# MCU.net
KiCad netlist of a schematic drawn in Altium Designer
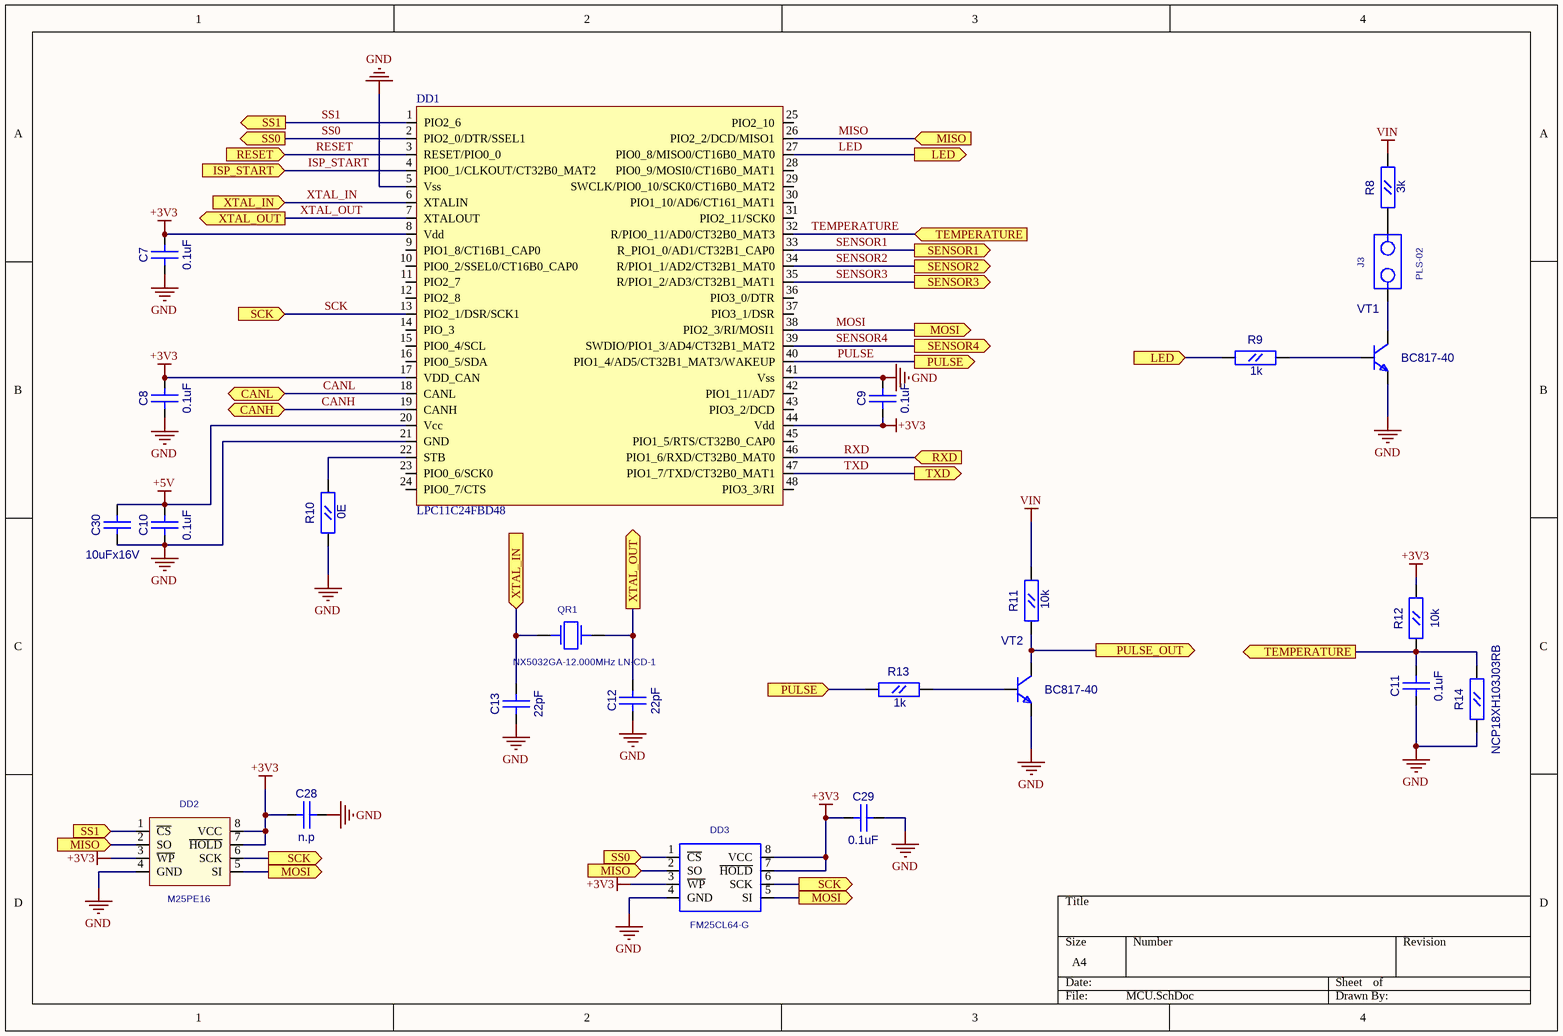
[diagram p0: MCU.SchDoc]

(export (version "E")
  (design (tool "Eeschema 10.0.6"))
  (components
    (comp (ref "C7")
      (value "0.1uF")
      (footprint "CC0603")
      (description "CC0603")
      (libsource (lib "gprs_modem_2") (part "CC0603"))
    )
    (comp (ref "C8")
      (value "0.1uF")
      (footprint "CC0603")
      (description "CC0603")
      (libsource (lib "gprs_modem_2") (part "CC0603"))
    )
    (comp (ref "C9")
      (value "0.1uF")
      (footprint "CC0603")
      (description "CC0603")
      (libsource (lib "gprs_modem_2") (part "CC0603"))
    )
    (comp (ref "C10")
      (value "0.1uF")
      (footprint "CC0603")
      (description "CC0603")
      (libsource (lib "gprs_modem_2") (part "CC0603"))
    )
    (comp (ref "C11")
      (value "0.1uF")
      (footprint "CC0603")
      (description "CC0603")
      (libsource (lib "gprs_modem_2") (part "CC0603"))
    )
    (comp (ref "C12")
      (value "22pF")
      (footprint "CC0603")
      (description "CC0603")
      (libsource (lib "gprs_modem_2") (part "CC0603"))
    )
    (comp (ref "C13")
      (value "22pF")
      (footprint "CC0603")
      (description "CC0603")
      (libsource (lib "gprs_modem_2") (part "CC0603"))
    )
    (comp (ref "C28")
      (value "n.p")
      (footprint "CC0603")
      (description "CC0603")
      (libsource (lib "gprs_modem_2") (part "CC0603"))
    )
    (comp (ref "C29")
      (value "0.1uF")
      (footprint "CC0603")
      (description "CC0603")
      (libsource (lib "gprs_modem_2") (part "CC0603"))
    )
    (comp (ref "C30")
      (value "10uFx16V")
      (footprint "CC0805")
      (description "CC0805")
      (libsource (lib "gprs_modem_2") (part "CC0805"))
    )
    (comp (ref "DD1")
      (value "LPC11C24FBD48")
      (footprint "LQFP-48")
      (libsource (lib "gprs_modem_2") (part "LPC11C24FBD48"))
    )
    (comp (ref "DD2")
      (value "M25PE16")
      (footprint "EIAJ_SO8")
      (description "S25FL016A0LMFI01")
      (libsource (lib "gprs_modem_2") (part "S25FL016A0LMFI01"))
    )
    (comp (ref "DD3")
      (value "FM25CL64-G")
      (footprint "SO-8")
      (libsource (lib "gprs_modem_2") (part "FM25CL64-G"))
    )
    (comp (ref "J3") (value "PLS-02") (footprint "PLS-02") (libsource (lib "gprs_modem_2") (part "PLS-02")))
    (comp (ref "QR1")
      (value "NX5032GA-12.000MHz LN-CD-1")
      (footprint "AC5032_2")
      (description "AC5032/2")
      (libsource (lib "gprs_modem_2") (part "AC5032_2"))
    )
    (comp (ref "R8")
      (value "3k")
      (footprint "RC0603")
      (description "RC0603")
      (libsource (lib "gprs_modem_2") (part "RC0603"))
    )
    (comp (ref "R9")
      (value "1k")
      (footprint "RC0603")
      (description "RC0603")
      (libsource (lib "gprs_modem_2") (part "RC0603"))
    )
    (comp (ref "R10")
      (value "0E")
      (footprint "RC0603")
      (description "RC0603")
      (libsource (lib "gprs_modem_2") (part "RC0603"))
    )
    (comp (ref "R11")
      (value "10k")
      (footprint "RC0603")
      (description "RC0603")
      (libsource (lib "gprs_modem_2") (part "RC0603"))
    )
    (comp (ref "R12")
      (value "10k")
      (footprint "RC0603")
      (description "RC0603")
      (libsource (lib "gprs_modem_2") (part "RC0603"))
    )
    (comp (ref "R13")
      (value "1k")
      (footprint "RC0603")
      (description "RC0603")
      (libsource (lib "gprs_modem_2") (part "RC0603"))
    )
    (comp (ref "R14")
      (value "NCP18XH103J03RB")
      (footprint "RC0603")
      (description "RC0603")
      (libsource (lib "gprs_modem_2") (part "RC0603"))
    )
    (comp (ref "VT1")
      (value "BC817-40")
      (footprint "SOT-23(123)")
      (description "NPN 500ma transistor")
      (libsource (lib "gprs_modem_2") (part "BC846BLT1"))
    )
    (comp (ref "VT2")
      (value "BC817-40")
      (footprint "SOT-23(123)")
      (description "NPN 500ma transistor")
      (libsource (lib "gprs_modem_2") (part "BC846BLT1"))
    )
  )
  (nets
    (net (code "1") (name "+3V3") (class "Default")
      (node (ref "C28") (pin "1") (pinfunction "A_1") (pintype "passive"))
      (node (ref "C29") (pin "1") (pinfunction "A_1") (pintype "passive"))
      (node (ref "C7") (pin "2") (pinfunction "B_2") (pintype "passive"))
      (node (ref "C8") (pin "2") (pinfunction "B_2") (pintype "passive"))
      (node (ref "C9") (pin "1") (pinfunction "A_1") (pintype "passive"))
      (node (ref "DD1") (pin "17") (pinfunction "VDD_CAN_17") (pintype "passive"))
      (node (ref "DD1") (pin "44") (pinfunction "Vdd_44") (pintype "passive"))
      (node (ref "DD1") (pin "8") (pinfunction "Vdd_8") (pintype "passive"))
      (node (ref "DD2") (pin "3") (pinfunction "~{WP}_3") (pintype "passive"))
      (node (ref "DD2") (pin "7") (pinfunction "~{HOLD}_7") (pintype "passive"))
      (node (ref "DD2") (pin "8") (pinfunction "VCC_8") (pintype "passive"))
      (node (ref "DD3") (pin "3") (pinfunction "~{WP}_3") (pintype "passive"))
      (node (ref "DD3") (pin "7") (pinfunction "~{HOLD}_7") (pintype "passive"))
      (node (ref "DD3") (pin "8") (pinfunction "VCC_8") (pintype "passive"))
      (node (ref "R12") (pin "2") (pinfunction "B_2") (pintype "passive"))
    )
    (net (code "2") (name "+5V") (class "Default")
      (node (ref "C10") (pin "2") (pinfunction "B_2") (pintype "passive"))
      (node (ref "C30") (pin "2") (pinfunction "B_2") (pintype "passive"))
      (node (ref "DD1") (pin "20") (pinfunction "Vcc_20") (pintype "passive"))
    )
    (net (code "3") (name "/CANH") (class "Default")
      (node (ref "DD1") (pin "19") (pinfunction "CANH_19") (pintype "passive"))
    )
    (net (code "4") (name "/CANL") (class "Default")
      (node (ref "DD1") (pin "18") (pinfunction "CANL_18") (pintype "passive"))
    )
    (net (code "5") (name "/ISP_START") (class "Default")
      (node (ref "DD1") (pin "4") (pinfunction "PIO0_1/CLKOUT/CT32B0_MAT2_4") (pintype "passive"))
    )
    (net (code "6") (name "/LED") (class "Default")
      (node (ref "DD1") (pin "27") (pinfunction "PIO0_8/MISO0/CT16B0_MAT0_27") (pintype "passive"))
      (node (ref "R9") (pin "1") (pinfunction "A_1") (pintype "passive"))
    )
    (net (code "7") (name "/MISO") (class "Default")
      (node (ref "DD1") (pin "26") (pinfunction "PIO2_2/DCD/MISO1_26") (pintype "passive"))
      (node (ref "DD2") (pin "2") (pinfunction "SO_2") (pintype "passive"))
      (node (ref "DD3") (pin "2") (pinfunction "SO_2") (pintype "passive"))
    )
    (net (code "8") (name "/MOSI") (class "Default")
      (node (ref "DD1") (pin "38") (pinfunction "PIO2_3/RI/MOSI1_38") (pintype "passive"))
      (node (ref "DD2") (pin "5") (pinfunction "SI_5") (pintype "passive"))
      (node (ref "DD3") (pin "5") (pinfunction "SI_5") (pintype "passive"))
    )
    (net (code "9") (name "/PULSE") (class "Default")
      (node (ref "DD1") (pin "40") (pinfunction "PIO1_4/AD5/CT32B1_MAT3/WAKEUP_40") (pintype "passive"))
      (node (ref "R13") (pin "1") (pinfunction "A_1") (pintype "passive"))
    )
    (net (code "10") (name "/PULSE_OUT") (class "Default")
      (node (ref "R11") (pin "1") (pinfunction "A_1") (pintype "passive"))
      (node (ref "VT2") (pin "3") (pinfunction "C_3") (pintype "passive"))
    )
    (net (code "11") (name "/RESET") (class "Default")
      (node (ref "DD1") (pin "3") (pinfunction "RESET/PIO0_0_3") (pintype "passive"))
    )
    (net (code "12") (name "/RXD") (class "Default")
      (node (ref "DD1") (pin "46") (pinfunction "PIO1_6/RXD/CT32B0_MAT0_46") (pintype "passive"))
    )
    (net (code "13") (name "/SCK") (class "Default")
      (node (ref "DD1") (pin "13") (pinfunction "PIO2_1/DSR/SCK1_13") (pintype "passive"))
      (node (ref "DD2") (pin "6") (pinfunction "SCK_6") (pintype "passive"))
      (node (ref "DD3") (pin "6") (pinfunction "SCK_6") (pintype "passive"))
    )
    (net (code "14") (name "/SENSOR1") (class "Default")
      (node (ref "DD1") (pin "33") (pinfunction "R_PIO1_0/AD1/CT32B1_CAP0_33") (pintype "passive"))
    )
    (net (code "15") (name "/SENSOR2") (class "Default")
      (node (ref "DD1") (pin "34") (pinfunction "R/PIO1_1/AD2/CT32B1_MAT0_34") (pintype "passive"))
    )
    (net (code "16") (name "/SENSOR3") (class "Default")
      (node (ref "DD1") (pin "35") (pinfunction "R/PIO1_2/AD3/CT32B1_MAT1_35") (pintype "passive"))
    )
    (net (code "17") (name "/SENSOR4") (class "Default")
      (node (ref "DD1") (pin "39") (pinfunction "SWDIO/PIO1_3/AD4/CT32B1_MAT2_39") (pintype "passive"))
    )
    (net (code "18") (name "/SS0") (class "Default")
      (node (ref "DD1") (pin "2") (pinfunction "PIO2_0/DTR/SSEL1_2") (pintype "passive"))
      (node (ref "DD3") (pin "1") (pinfunction "~{CS}_1") (pintype "passive"))
    )
    (net (code "19") (name "/SS1") (class "Default")
      (node (ref "DD1") (pin "1") (pinfunction "PIO2_6_1") (pintype "passive"))
      (node (ref "DD2") (pin "1") (pinfunction "~{CS}_1") (pintype "passive"))
    )
    (net (code "20") (name "/TEMPERATURE") (class "Default")
      (node (ref "C11") (pin "2") (pinfunction "B_2") (pintype "passive"))
      (node (ref "DD1") (pin "32") (pinfunction "R/PIO0_11/AD0/CT32B0_MAT3_32") (pintype "passive"))
      (node (ref "R12") (pin "1") (pinfunction "A_1") (pintype "passive"))
      (node (ref "R14") (pin "2") (pinfunction "B_2") (pintype "passive"))
    )
    (net (code "21") (name "/TXD") (class "Default")
      (node (ref "DD1") (pin "47") (pinfunction "PIO1_7/TXD/CT32B0_MAT1_47") (pintype "passive"))
    )
    (net (code "22") (name "/XTAL_IN") (class "Default")
      (node (ref "C13") (pin "2") (pinfunction "B_2") (pintype "passive"))
      (node (ref "DD1") (pin "6") (pinfunction "XTALIN_6") (pintype "passive"))
      (node (ref "QR1") (pin "1") (pintype "passive"))
    )
    (net (code "23") (name "/XTAL_OUT") (class "Default")
      (node (ref "C12") (pin "2") (pinfunction "B_2") (pintype "passive"))
      (node (ref "DD1") (pin "7") (pinfunction "XTALOUT_7") (pintype "passive"))
      (node (ref "QR1") (pin "2") (pintype "passive"))
    )
    (net (code "24") (name "GND") (class "Default")
      (node (ref "C10") (pin "1") (pinfunction "A_1") (pintype "passive"))
      (node (ref "C11") (pin "1") (pinfunction "A_1") (pintype "passive"))
      (node (ref "C12") (pin "1") (pinfunction "A_1") (pintype "passive"))
      (node (ref "C13") (pin "1") (pinfunction "A_1") (pintype "passive"))
      (node (ref "C28") (pin "2") (pinfunction "B_2") (pintype "passive"))
      (node (ref "C29") (pin "2") (pinfunction "B_2") (pintype "passive"))
      (node (ref "C30") (pin "1") (pinfunction "A_1") (pintype "passive"))
      (node (ref "C7") (pin "1") (pinfunction "A_1") (pintype "passive"))
      (node (ref "C8") (pin "1") (pinfunction "A_1") (pintype "passive"))
      (node (ref "C9") (pin "2") (pinfunction "B_2") (pintype "passive"))
      (node (ref "DD1") (pin "21") (pinfunction "GND_21") (pintype "passive"))
      (node (ref "DD1") (pin "41") (pinfunction "Vss_41") (pintype "passive"))
      (node (ref "DD1") (pin "5") (pinfunction "Vss_5") (pintype "passive"))
      (node (ref "DD2") (pin "4") (pinfunction "GND_4") (pintype "passive"))
      (node (ref "DD3") (pin "4") (pinfunction "GND_4") (pintype "passive"))
      (node (ref "R10") (pin "1") (pinfunction "A_1") (pintype "passive"))
      (node (ref "R14") (pin "1") (pinfunction "A_1") (pintype "passive"))
      (node (ref "VT1") (pin "2") (pinfunction "E_2") (pintype "passive"))
      (node (ref "VT2") (pin "2") (pinfunction "E_2") (pintype "passive"))
    )
    (net (code "25") (name "Net-(DD1-STB)") (class "Default")
      (node (ref "DD1") (pin "22") (pinfunction "STB_22") (pintype "passive"))
      (node (ref "R10") (pin "2") (pinfunction "B_2") (pintype "passive"))
    )
    (net (code "26") (name "Net-(R8-A)") (class "Default")
      (node (ref "J3") (pin "2") (pintype "passive"))
      (node (ref "R8") (pin "1") (pinfunction "A_1") (pintype "passive"))
    )
    (net (code "27") (name "Net-(R9-B)") (class "Default")
      (node (ref "R9") (pin "2") (pinfunction "B_2") (pintype "passive"))
      (node (ref "VT1") (pin "1") (pinfunction "B_1") (pintype "passive"))
    )
    (net (code "28") (name "Net-(R13-B)") (class "Default")
      (node (ref "R13") (pin "2") (pinfunction "B_2") (pintype "passive"))
      (node (ref "VT2") (pin "1") (pinfunction "B_1") (pintype "passive"))
    )
    (net (code "29") (name "Net-(VT1-C)") (class "Default")
      (node (ref "J3") (pin "1") (pintype "passive"))
      (node (ref "VT1") (pin "3") (pinfunction "C_3") (pintype "passive"))
    )
    (net (code "30") (name "VIN") (class "Default")
      (node (ref "R11") (pin "2") (pinfunction "B_2") (pintype "passive"))
      (node (ref "R8") (pin "2") (pinfunction "B_2") (pintype "passive"))
    )
    (net (code "31") (name "unconnected-(DD1-PIO0_2{slash}SSEL0{slash}CT16B0_CAP0-Pad10)") (class "Default")
      (node (ref "DD1") (pin "10") (pinfunction "PIO0_2/SSEL0/CT16B0_CAP0_10") (pintype "passive"))
    )
    (net (code "32") (name "unconnected-(DD1-PIO0_4{slash}SCL-Pad15)") (class "Default")
      (node (ref "DD1") (pin "15") (pinfunction "PIO0_4/SCL_15") (pintype "passive"))
    )
    (net (code "33") (name "unconnected-(DD1-PIO0_5{slash}SDA-Pad16)") (class "Default")
      (node (ref "DD1") (pin "16") (pinfunction "PIO0_5/SDA_16") (pintype "passive"))
    )
    (net (code "34") (name "unconnected-(DD1-PIO0_6{slash}SCK0-Pad23)") (class "Default")
      (node (ref "DD1") (pin "23") (pinfunction "PIO0_6/SCK0_23") (pintype "passive"))
    )
    (net (code "35") (name "unconnected-(DD1-PIO0_7{slash}CTS-Pad24)") (class "Default")
      (node (ref "DD1") (pin "24") (pinfunction "PIO0_7/CTS_24") (pintype "passive"))
    )
    (net (code "36") (name "unconnected-(DD1-PIO0_9{slash}MOSI0{slash}CT16B0_MAT1-Pad28)") (class "Default")
      (node (ref "DD1") (pin "28") (pinfunction "PIO0_9/MOSI0/CT16B0_MAT1_28") (pintype "passive"))
    )
    (net (code "37") (name "unconnected-(DD1-PIO1_5{slash}RTS{slash}CT32B0_CAP0-Pad45)") (class "Default")
      (node (ref "DD1") (pin "45") (pinfunction "PIO1_5/RTS/CT32B0_CAP0_45") (pintype "passive"))
    )
    (net (code "38") (name "unconnected-(DD1-PIO1_8{slash}CT16B1_CAP0-Pad9)") (class "Default")
      (node (ref "DD1") (pin "9") (pinfunction "PIO1_8/CT16B1_CAP0_9") (pintype "passive"))
    )
    (net (code "39") (name "unconnected-(DD1-PIO1_10{slash}AD6{slash}CT161_MAT1-Pad30)") (class "Default")
      (node (ref "DD1") (pin "30") (pinfunction "PIO1_10/AD6/CT161_MAT1_30") (pintype "passive"))
    )
    (net (code "40") (name "unconnected-(DD1-PIO1_11{slash}AD7-Pad42)") (class "Default")
      (node (ref "DD1") (pin "42") (pinfunction "PIO1_11/AD7_42") (pintype "passive"))
    )
    (net (code "41") (name "unconnected-(DD1-PIO2_7-Pad11)") (class "Default")
      (node (ref "DD1") (pin "11") (pinfunction "PIO2_7_11") (pintype "passive"))
    )
    (net (code "42") (name "unconnected-(DD1-PIO2_8-Pad12)") (class "Default")
      (node (ref "DD1") (pin "12") (pinfunction "PIO2_8_12") (pintype "passive"))
    )
    (net (code "43") (name "unconnected-(DD1-PIO2_10-Pad25)") (class "Default")
      (node (ref "DD1") (pin "25") (pinfunction "PIO2_10_25") (pintype "passive"))
    )
    (net (code "44") (name "unconnected-(DD1-PIO2_11{slash}SCK0-Pad31)") (class "Default")
      (node (ref "DD1") (pin "31") (pinfunction "PIO2_11/SCK0_31") (pintype "passive"))
    )
    (net (code "45") (name "unconnected-(DD1-PIO3_0{slash}DTR-Pad36)") (class "Default")
      (node (ref "DD1") (pin "36") (pinfunction "PIO3_0/DTR_36") (pintype "passive"))
    )
    (net (code "46") (name "unconnected-(DD1-PIO3_1{slash}DSR-Pad37)") (class "Default")
      (node (ref "DD1") (pin "37") (pinfunction "PIO3_1/DSR_37") (pintype "passive"))
    )
    (net (code "47") (name "unconnected-(DD1-PIO3_2{slash}DCD-Pad43)") (class "Default")
      (node (ref "DD1") (pin "43") (pinfunction "PIO3_2/DCD_43") (pintype "passive"))
    )
    (net (code "48") (name "unconnected-(DD1-PIO3_3{slash}RI-Pad48)") (class "Default")
      (node (ref "DD1") (pin "48") (pinfunction "PIO3_3/RI_48") (pintype "passive"))
    )
    (net (code "49") (name "unconnected-(DD1-PIO_3-Pad14)") (class "Default")
      (node (ref "DD1") (pin "14") (pinfunction "PIO_3_14") (pintype "passive"))
    )
    (net (code "50") (name "unconnected-(DD1-SWCLK{slash}PIO0_10{slash}SCK0{slash}CT16B0_MAT2-Pad29)") (class "Default")
      (node (ref "DD1") (pin "29") (pinfunction "SWCLK/PIO0_10/SCK0/CT16B0_MAT2_29") (pintype "passive"))
    )
  )
)
